# ANIMA_Small_Scale.net
KiCad netlist of a schematic drawn in EAGLE
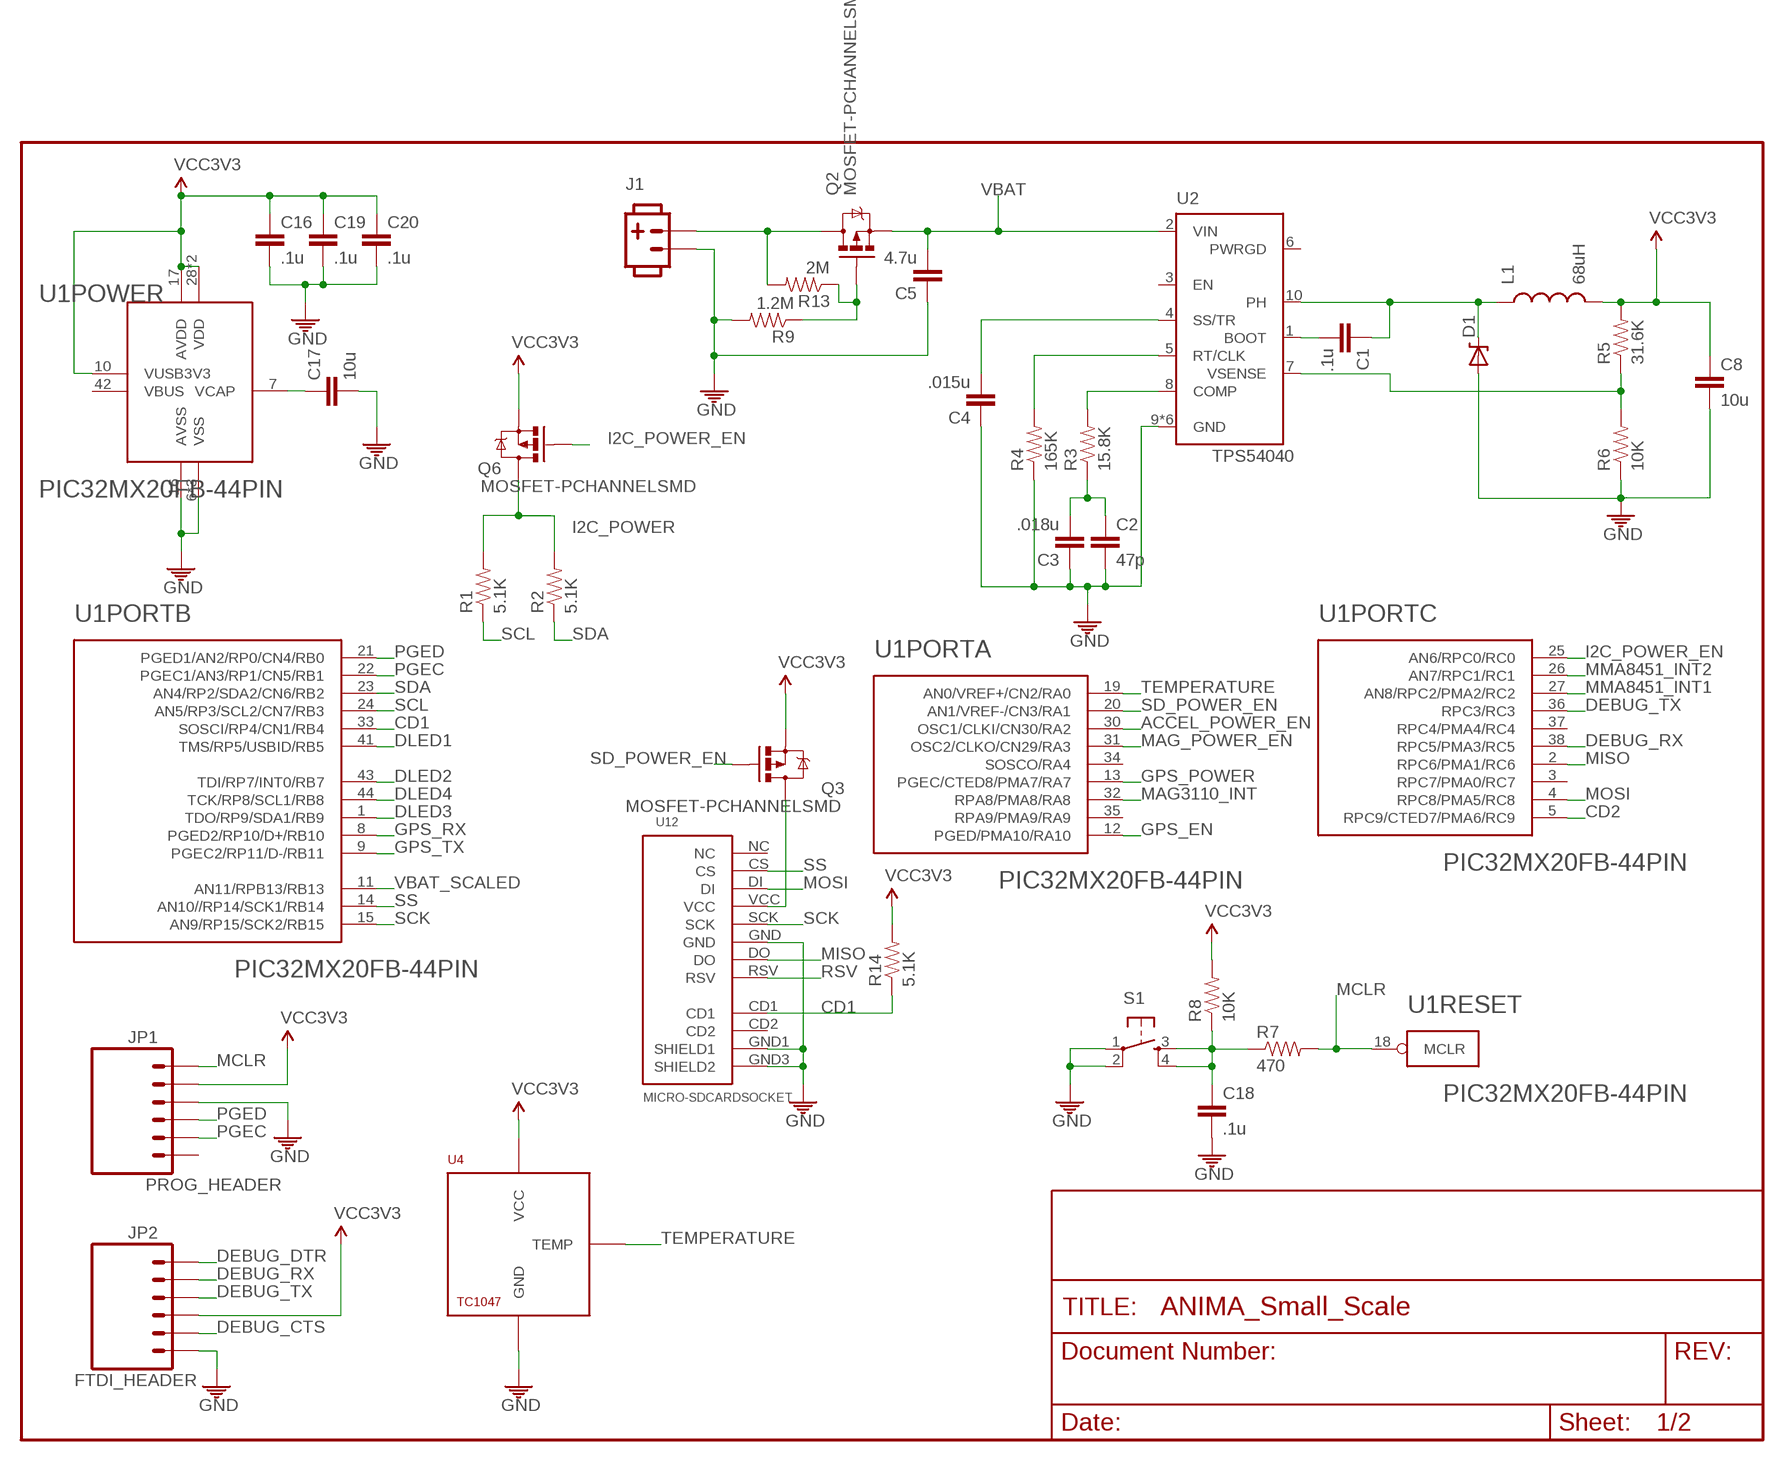
[diagram p0: schematic, sheet 1]
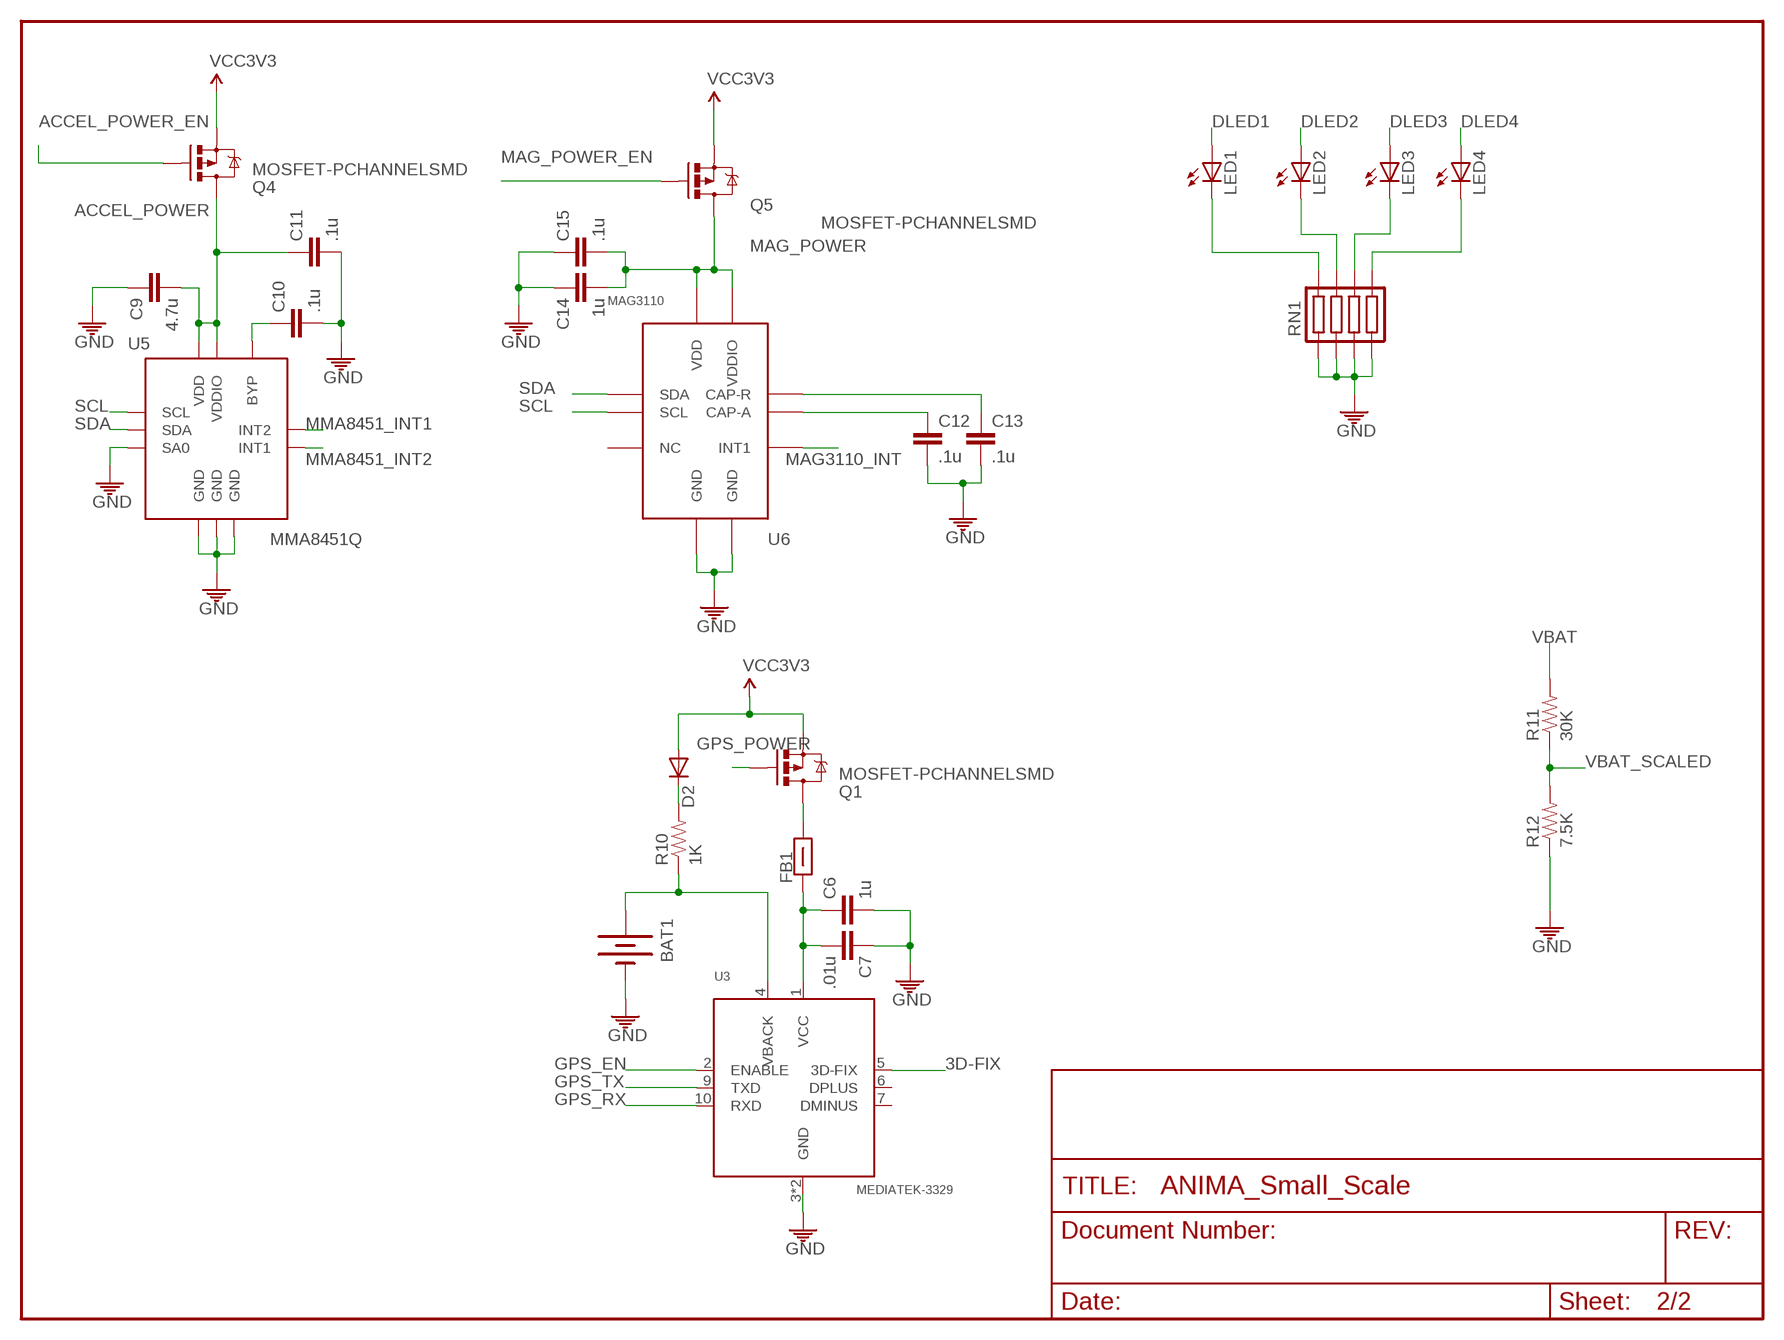
[diagram p1: schematic, sheet 2]

(export (version "E")
  (design (tool "Eeschema 10.0.6"))
  (components
    (comp (ref "BAT1")
      (value "BATTERY4.8MMSMD")
      (footprint "eagle-import:MS412FE-FL26E")
      (libsource (lib "eagle-import") (part "BATTERY4.8MMSMD"))
    )
    (comp (ref "C6")
      (value "1u")
      (footprint "eagle-import:0805")
      (libsource (lib "eagle-import") (part "CAP0805"))
    )
    (comp (ref "C7")
      (value ".01u")
      (footprint "eagle-import:0805")
      (libsource (lib "eagle-import") (part "CAP0805"))
    )
    (comp (ref "C9")
      (value "4.7u")
      (footprint "eagle-import:0805")
      (libsource (lib "eagle-import") (part "CAP0805"))
    )
    (comp (ref "C10")
      (value ".1u")
      (footprint "eagle-import:0805")
      (libsource (lib "eagle-import") (part "CAP0805"))
    )
    (comp (ref "C11")
      (value ".1u")
      (footprint "eagle-import:0805")
      (libsource (lib "eagle-import") (part "CAP0805"))
    )
    (comp (ref "C12")
      (value ".1u")
      (footprint "eagle-import:0805")
      (libsource (lib "eagle-import") (part "CAP0805"))
    )
    (comp (ref "C13")
      (value ".1u")
      (footprint "eagle-import:0805")
      (libsource (lib "eagle-import") (part "CAP0805"))
    )
    (comp (ref "C14")
      (value "1u")
      (footprint "eagle-import:0805")
      (libsource (lib "eagle-import") (part "CAP0805"))
    )
    (comp (ref "C15")
      (value ".1u")
      (footprint "eagle-import:0805")
      (libsource (lib "eagle-import") (part "CAP0805"))
    )
    (comp (ref "D2")
      (value "DIODESMA")
      (footprint "eagle-import:SMA-DIODE")
      (libsource (lib "eagle-import") (part "DIODESMA"))
    )
    (comp (ref "FB1")
      (value "FERRITE_BEAD")
      (footprint "eagle-import:0603")
      (libsource (lib "eagle-import") (part "FERRITE_BEAD"))
    )
    (comp (ref "LED1")
      (value "LED1206")
      (footprint "eagle-import:LED-1206")
      (libsource (lib "eagle-import") (part "LED1206"))
    )
    (comp (ref "LED2")
      (value "LED1206")
      (footprint "eagle-import:LED-1206")
      (libsource (lib "eagle-import") (part "LED1206"))
    )
    (comp (ref "LED3")
      (value "LED1206")
      (footprint "eagle-import:LED-1206")
      (libsource (lib "eagle-import") (part "LED1206"))
    )
    (comp (ref "LED4")
      (value "LED1206")
      (footprint "eagle-import:LED-1206")
      (libsource (lib "eagle-import") (part "LED1206"))
    )
    (comp (ref "Q1")
      (value "MOSFET-PCHANNELSMD")
      (footprint "eagle-import:SOT23-3")
      (libsource (lib "eagle-import") (part "MOSFET-PCHANNELSMD"))
    )
    (comp (ref "Q4")
      (value "MOSFET-PCHANNELSMD")
      (footprint "eagle-import:SOT23-3")
      (libsource (lib "eagle-import") (part "MOSFET-PCHANNELSMD"))
    )
    (comp (ref "Q5")
      (value "MOSFET-PCHANNELSMD")
      (footprint "eagle-import:SOT23-3")
      (libsource (lib "eagle-import") (part "MOSFET-PCHANNELSMD"))
    )
    (comp (ref "R10")
      (value "1K")
      (footprint "eagle-import:0805")
      (libsource (lib "eagle-import") (part "RESISTOR0805-RES"))
    )
    (comp (ref "R11")
      (value "30K")
      (footprint "eagle-import:0805")
      (libsource (lib "eagle-import") (part "RESISTOR0805-RES"))
    )
    (comp (ref "R12")
      (value "7.5K")
      (footprint "eagle-import:0805")
      (libsource (lib "eagle-import") (part "RESISTOR0805-RES"))
    )
    (comp (ref "RN1")
      (value "RESISTOR_ARRAY-4")
      (footprint "eagle-import:EXB-38V271JV")
      (libsource (lib "eagle-import") (part "RESISTOR_ARRAY-4"))
    )
    (comp (ref "U3")
      (value "MEDIATEK-3329")
      (footprint "eagle-import:MEDIATEK-3329")
      (libsource (lib "eagle-import") (part "MEDIATEK-3329"))
    )
    (comp (ref "U5")
      (value "MMA8451Q")
      (footprint "eagle-import:QFN-16_FREE")
      (libsource (lib "eagle-import") (part "MMA8451Q"))
    )
    (comp (ref "U6")
      (value "MAG3110")
      (footprint "eagle-import:DFN-10_FREE")
      (libsource (lib "eagle-import") (part "MAG3110"))
    )
    (comp (ref "C1")
      (value ".1u")
      (footprint "eagle-import:0805")
      (libsource (lib "eagle-import") (part "CAP0805"))
    )
    (comp (ref "C2")
      (value "47p")
      (footprint "eagle-import:0805")
      (libsource (lib "eagle-import") (part "CAP0805"))
    )
    (comp (ref "C3")
      (value ".018u")
      (footprint "eagle-import:0805")
      (libsource (lib "eagle-import") (part "CAP0805"))
    )
    (comp (ref "C4")
      (value ".015u")
      (footprint "eagle-import:0805")
      (libsource (lib "eagle-import") (part "CAP0805"))
    )
    (comp (ref "C5")
      (value "4.7u")
      (footprint "eagle-import:0805")
      (libsource (lib "eagle-import") (part "CAP0805"))
    )
    (comp (ref "C8")
      (value "10u")
      (footprint "eagle-import:1206")
      (libsource (lib "eagle-import") (part "CAP1206"))
    )
    (comp (ref "C16")
      (value ".1u")
      (footprint "eagle-import:0805")
      (libsource (lib "eagle-import") (part "CAP0805"))
    )
    (comp (ref "C17")
      (value "10u")
      (footprint "eagle-import:0805")
      (libsource (lib "eagle-import") (part "CAP0805"))
    )
    (comp (ref "C18")
      (value ".1u")
      (footprint "eagle-import:0805")
      (libsource (lib "eagle-import") (part "CAP0805"))
    )
    (comp (ref "C19")
      (value ".1u")
      (footprint "eagle-import:0805")
      (libsource (lib "eagle-import") (part "CAP0805"))
    )
    (comp (ref "C20")
      (value ".1u")
      (footprint "eagle-import:0805")
      (libsource (lib "eagle-import") (part "CAP0805"))
    )
    (comp (ref "D1")
      (value "DIODE-ZENER1")
      (footprint "eagle-import:SOD523")
      (libsource (lib "eagle-import") (part "DIODE-ZENER1"))
    )
    (comp (ref "J1")
      (value "POW_CONNECTFEMALE-RA")
      (footprint "eagle-import:SOCKET-FEMALE_RA-3.96MM-2")
      (libsource (lib "eagle-import") (part "POW_CONNECTFEMALE-RA"))
    )
    (comp (ref "JP1")
      (value "M06FEMALE_LOCK")
      (footprint "eagle-import:1X06_FEMALE_LOCK.010")
      (libsource (lib "eagle-import") (part "M06FEMALE_LOCK"))
    )
    (comp (ref "JP2")
      (value "M06FEMALE_LOCK")
      (footprint "eagle-import:1X06_FEMALE_LOCK.010")
      (libsource (lib "eagle-import") (part "M06FEMALE_LOCK"))
    )
    (comp (ref "L1")
      (value "68uH")
      (footprint "eagle-import:ELL-CTVV")
      (libsource (lib "eagle-import") (part "INDUCTORELL-CTVV"))
    )
    (comp (ref "Q2")
      (value "MOSFET-PCHANNELSMD")
      (footprint "eagle-import:SOT23-3")
      (libsource (lib "eagle-import") (part "MOSFET-PCHANNELSMD"))
    )
    (comp (ref "Q3")
      (value "MOSFET-PCHANNELSMD")
      (footprint "eagle-import:SOT23-3")
      (libsource (lib "eagle-import") (part "MOSFET-PCHANNELSMD"))
    )
    (comp (ref "Q6")
      (value "MOSFET-PCHANNELSMD")
      (footprint "eagle-import:SOT23-3")
      (libsource (lib "eagle-import") (part "MOSFET-PCHANNELSMD"))
    )
    (comp (ref "R1")
      (value "5.1K")
      (footprint "eagle-import:0805")
      (libsource (lib "eagle-import") (part "RESISTOR0805-RES"))
    )
    (comp (ref "R2")
      (value "5.1K")
      (footprint "eagle-import:0805")
      (libsource (lib "eagle-import") (part "RESISTOR0805-RES"))
    )
    (comp (ref "R3")
      (value "15.8K")
      (footprint "eagle-import:0805")
      (libsource (lib "eagle-import") (part "RESISTOR0805-RES"))
    )
    (comp (ref "R4")
      (value "165K")
      (footprint "eagle-import:0805")
      (libsource (lib "eagle-import") (part "RESISTOR0805-RES"))
    )
    (comp (ref "R5")
      (value "31.6K")
      (footprint "eagle-import:0805")
      (libsource (lib "eagle-import") (part "RESISTOR0805-RES"))
    )
    (comp (ref "R6")
      (value "10K")
      (footprint "eagle-import:0805")
      (libsource (lib "eagle-import") (part "RESISTOR0805-RES"))
    )
    (comp (ref "R7")
      (value "470")
      (footprint "eagle-import:0805")
      (libsource (lib "eagle-import") (part "RESISTOR0805-RES"))
    )
    (comp (ref "R8")
      (value "10K")
      (footprint "eagle-import:0805")
      (libsource (lib "eagle-import") (part "RESISTOR0805-RES"))
    )
    (comp (ref "R9")
      (value "1.2M")
      (footprint "eagle-import:0805")
      (libsource (lib "eagle-import") (part "RESISTOR0805-RES"))
    )
    (comp (ref "R13")
      (value "2M")
      (footprint "eagle-import:0805")
      (libsource (lib "eagle-import") (part "RESISTOR0805-RES"))
    )
    (comp (ref "R14")
      (value "5.1K")
      (footprint "eagle-import:0805")
      (libsource (lib "eagle-import") (part "RESISTOR0805-RES"))
    )
    (comp (ref "S1")
      (value "TAC_SWITCHPTH")
      (footprint "eagle-import:B3F-1020")
      (libsource (lib "eagle-import") (part "TAC_SWITCHPTH"))
    )
    (comp (ref "U1")
      (value "PIC32MX20FB-44PIN")
      (footprint "eagle-import:TQFP44")
      (libsource (lib "eagle-import") (part "PIC32MX20FB-44PIN"))
    )
    (comp (ref "U2")
      (value "TPS54040")
      (footprint "eagle-import:MSOP-10-GNDPAD")
      (libsource (lib "eagle-import") (part "TPS54040"))
    )
    (comp (ref "U4")
      (value "TC1047")
      (footprint "eagle-import:SOT-23B")
      (libsource (lib "eagle-import") (part "TC1047"))
    )
    (comp (ref "U12")
      (value "MICRO-SDCARDSOCKET")
      (footprint "eagle-import:MICRO-SD-SOCKET-PP")
      (libsource (lib "eagle-import") (part "MICRO-SDCARDSOCKET"))
    )
  )
  (nets
    (net (code "1") (name "3D-FIX") (class "Default")
      (node (ref "U3") (pin "5") (pinfunction "3D-FIX_5") (pintype "output"))
    )
    (net (code "2") (name "ACCEL_POWER") (class "Default")
      (node (ref "C11") (pin "1") (pinfunction "1_1") (pintype "passive"))
      (node (ref "C9") (pin "2") (pinfunction "2_2") (pintype "passive"))
      (node (ref "Q4") (pin "3") (pinfunction "D_3") (pintype "passive"))
      (node (ref "U5") (pin "P$1") (pinfunction "VDDIO_P$1") (pintype "passive"))
      (node (ref "U5") (pin "P$14") (pinfunction "VDD_P$14") (pintype "passive"))
    )
    (net (code "3") (name "ACCEL_POWER_EN") (class "Default")
      (node (ref "Q4") (pin "1") (pinfunction "G_1") (pintype "passive"))
      (node (ref "U1") (pin "30") (pinfunction "OSC1/CLKI/CN30/RA2_30") (pintype "bidirectional"))
    )
    (net (code "4") (name "CD1") (class "Default")
      (node (ref "R14") (pin "1") (pinfunction "1_1") (pintype "passive"))
      (node (ref "U1") (pin "33") (pinfunction "SOSCI/RP4/CN1/RB4_33") (pintype "bidirectional"))
      (node (ref "U12") (pin "CD1") (pinfunction "CD1_CD1") (pintype "bidirectional"))
    )
    (net (code "5") (name "CD2") (class "Default")
      (node (ref "U1") (pin "5") (pinfunction "RPC9/CTED7/PMA6/RC9_5") (pintype "bidirectional"))
    )
    (net (code "6") (name "DEBUG_CTS") (class "Default")
      (node (ref "JP2") (pin "5") (pinfunction "5_5") (pintype "passive"))
    )
    (net (code "7") (name "DEBUG_DTR") (class "Default")
      (node (ref "JP2") (pin "1") (pinfunction "1_1") (pintype "passive"))
    )
    (net (code "8") (name "DEBUG_RX") (class "Default")
      (node (ref "JP2") (pin "2") (pinfunction "2_2") (pintype "passive"))
      (node (ref "U1") (pin "38") (pinfunction "RPC5/PMA3/RC5_38") (pintype "bidirectional"))
    )
    (net (code "9") (name "DEBUG_TX") (class "Default")
      (node (ref "JP2") (pin "3") (pinfunction "3_3") (pintype "passive"))
      (node (ref "U1") (pin "36") (pinfunction "RPC3/RC3_36") (pintype "bidirectional"))
    )
    (net (code "10") (name "DLED1") (class "Default")
      (node (ref "LED1") (pin "A") (pinfunction "A_A") (pintype "passive"))
      (node (ref "U1") (pin "41") (pinfunction "TMS/RP5/USBID/RB5_41") (pintype "bidirectional"))
    )
    (net (code "11") (name "DLED2") (class "Default")
      (node (ref "LED2") (pin "A") (pinfunction "A_A") (pintype "passive"))
      (node (ref "U1") (pin "43") (pinfunction "TDI/RP7/INT0/RB7_43") (pintype "bidirectional"))
    )
    (net (code "12") (name "DLED3") (class "Default")
      (node (ref "LED3") (pin "A") (pinfunction "A_A") (pintype "passive"))
      (node (ref "U1") (pin "1") (pinfunction "TDO/RP9/SDA1/RB9_1") (pintype "bidirectional"))
    )
    (net (code "13") (name "DLED4") (class "Default")
      (node (ref "LED4") (pin "A") (pinfunction "A_A") (pintype "passive"))
      (node (ref "U1") (pin "44") (pinfunction "TCK/RP8/SCL1/RB8_44") (pintype "bidirectional"))
    )
    (net (code "14") (name "GND") (class "Default")
      (node (ref "BAT1") (pin "-") (pinfunction "-_-") (pintype "power_in"))
      (node (ref "C10") (pin "2") (pinfunction "2_2") (pintype "passive"))
      (node (ref "C11") (pin "2") (pinfunction "2_2") (pintype "passive"))
      (node (ref "C12") (pin "2") (pinfunction "2_2") (pintype "passive"))
      (node (ref "C13") (pin "2") (pinfunction "2_2") (pintype "passive"))
      (node (ref "C14") (pin "1") (pinfunction "1_1") (pintype "passive"))
      (node (ref "C15") (pin "1") (pinfunction "1_1") (pintype "passive"))
      (node (ref "C16") (pin "2") (pinfunction "2_2") (pintype "passive"))
      (node (ref "C17") (pin "2") (pinfunction "2_2") (pintype "passive"))
      (node (ref "C18") (pin "2") (pinfunction "2_2") (pintype "passive"))
      (node (ref "C19") (pin "2") (pinfunction "2_2") (pintype "passive"))
      (node (ref "C2") (pin "2") (pinfunction "2_2") (pintype "passive"))
      (node (ref "C20") (pin "2") (pinfunction "2_2") (pintype "passive"))
      (node (ref "C3") (pin "1") (pinfunction "1_1") (pintype "passive"))
      (node (ref "C4") (pin "1") (pinfunction "1_1") (pintype "passive"))
      (node (ref "C5") (pin "1") (pinfunction "1_1") (pintype "passive"))
      (node (ref "C6") (pin "2") (pinfunction "2_2") (pintype "passive"))
      (node (ref "C7") (pin "1") (pinfunction "1_1") (pintype "passive"))
      (node (ref "C8") (pin "2") (pinfunction "2_2") (pintype "passive"))
      (node (ref "C9") (pin "1") (pinfunction "1_1") (pintype "passive"))
      (node (ref "D1") (pin "-") (pinfunction "A_-") (pintype "passive"))
      (node (ref "J1") (pin "2") (pinfunction "2_2") (pintype "passive"))
      (node (ref "JP1") (pin "3") (pinfunction "3_3") (pintype "passive"))
      (node (ref "JP2") (pin "6") (pinfunction "6_6") (pintype "passive"))
      (node (ref "R12") (pin "1") (pinfunction "1_1") (pintype "passive"))
      (node (ref "R4") (pin "1") (pinfunction "1_1") (pintype "passive"))
      (node (ref "R6") (pin "1") (pinfunction "1_1") (pintype "passive"))
      (node (ref "R9") (pin "2") (pinfunction "2_2") (pintype "passive"))
      (node (ref "RN1") (pin "P$1") (pinfunction "1_P$1") (pintype "passive"))
      (node (ref "RN1") (pin "P$2") (pinfunction "2_P$2") (pintype "passive"))
      (node (ref "RN1") (pin "P$3") (pinfunction "3_P$3") (pintype "passive"))
      (node (ref "RN1") (pin "P$4") (pinfunction "4_P$4") (pintype "passive"))
      (node (ref "S1") (pin "1") (pinfunction "1_1") (pintype "passive"))
      (node (ref "S1") (pin "2") (pinfunction "2_2") (pintype "passive"))
      (node (ref "U1") (pin "16") (pinfunction "AVSS_16") (pintype "bidirectional"))
      (node (ref "U1") (pin "29") (pinfunction "VSS_29") (pintype "bidirectional"))
      (node (ref "U1") (pin "39") (pinfunction "VSS_39") (pintype "bidirectional"))
      (node (ref "U1") (pin "6") (pinfunction "VSS_6") (pintype "bidirectional"))
      (node (ref "U12") (pin "GND") (pinfunction "GND_GND") (pintype "bidirectional"))
      (node (ref "U12") (pin "GND1") (pinfunction "SHIELD1_GND1") (pintype "bidirectional"))
      (node (ref "U12") (pin "GND3") (pinfunction "SHIELD2_GND3") (pintype "bidirectional"))
      (node (ref "U2") (pin "9") (pinfunction "GND_9") (pintype "power_in"))
      (node (ref "U2") (pin "GND") (pinfunction "GND_GND") (pintype "power_in"))
      (node (ref "U2") (pin "GND@1") (pinfunction "GND_GND@1") (pintype "power_in"))
      (node (ref "U2") (pin "GND@2") (pinfunction "GND_GND@2") (pintype "power_in"))
      (node (ref "U2") (pin "GND@3") (pinfunction "GND_GND@3") (pintype "power_in"))
      (node (ref "U2") (pin "GND@4") (pinfunction "GND_GND@4") (pintype "power_in"))
      (node (ref "U3") (pin "3") (pinfunction "GND_3") (pintype "power_in"))
      (node (ref "U3") (pin "8") (pinfunction "GND_8") (pintype "power_in"))
      (node (ref "U4") (pin "P$3") (pinfunction "GND_P$3") (pintype "power_in"))
      (node (ref "U5") (pin "P$10") (pinfunction "GND_P$10") (pintype "passive"))
      (node (ref "U5") (pin "P$12") (pinfunction "GND_P$12") (pintype "passive"))
      (node (ref "U5") (pin "P$5") (pinfunction "GND_P$5") (pintype "passive"))
      (node (ref "U5") (pin "P$7") (pinfunction "SA0_P$7") (pintype "bidirectional"))
      (node (ref "U6") (pin "P$10") (pinfunction "GND_P$10") (pintype "passive"))
      (node (ref "U6") (pin "P$5") (pinfunction "GND_P$5") (pintype "passive"))
    )
    (net (code "15") (name "GPS_EN") (class "Default")
      (node (ref "U1") (pin "12") (pinfunction "PGED/PMA10/RA10_12") (pintype "bidirectional"))
      (node (ref "U3") (pin "2") (pinfunction "ENABLE_2") (pintype "input"))
    )
    (net (code "16") (name "GPS_POWER") (class "Default")
      (node (ref "Q1") (pin "1") (pinfunction "G_1") (pintype "passive"))
      (node (ref "U1") (pin "13") (pinfunction "PGEC/CTED8/PMA7/RA7_13") (pintype "bidirectional"))
    )
    (net (code "17") (name "GPS_RX") (class "Default")
      (node (ref "U1") (pin "8") (pinfunction "PGED2/RP10/D+/RB10_8") (pintype "bidirectional"))
      (node (ref "U3") (pin "10") (pinfunction "RXD_10") (pintype "input"))
    )
    (net (code "18") (name "GPS_TX") (class "Default")
      (node (ref "U1") (pin "9") (pinfunction "PGEC2/RP11/D-/RB11_9") (pintype "bidirectional"))
      (node (ref "U3") (pin "9") (pinfunction "TXD_9") (pintype "output"))
    )
    (net (code "19") (name "I2C_POWER") (class "Default")
      (node (ref "Q6") (pin "3") (pinfunction "D_3") (pintype "passive"))
      (node (ref "R1") (pin "2") (pinfunction "2_2") (pintype "passive"))
      (node (ref "R2") (pin "2") (pinfunction "2_2") (pintype "passive"))
    )
    (net (code "20") (name "I2C_POWER_EN") (class "Default")
      (node (ref "Q6") (pin "1") (pinfunction "G_1") (pintype "passive"))
      (node (ref "U1") (pin "25") (pinfunction "AN6/RPC0/RC0_25") (pintype "bidirectional"))
    )
    (net (code "21") (name "MAG3110_INT") (class "Default")
      (node (ref "U1") (pin "32") (pinfunction "RPA8/PMA8/RA8_32") (pintype "bidirectional"))
      (node (ref "U6") (pin "P$9") (pinfunction "INT1_P$9") (pintype "passive"))
    )
    (net (code "22") (name "MAG_POWER") (class "Default")
      (node (ref "C14") (pin "2") (pinfunction "2_2") (pintype "passive"))
      (node (ref "C15") (pin "2") (pinfunction "2_2") (pintype "passive"))
      (node (ref "Q5") (pin "3") (pinfunction "D_3") (pintype "passive"))
      (node (ref "U6") (pin "P$2") (pinfunction "VDD_P$2") (pintype "passive"))
      (node (ref "U6") (pin "P$8") (pinfunction "VDDIO_P$8") (pintype "passive"))
    )
    (net (code "23") (name "MAG_POWER_EN") (class "Default")
      (node (ref "Q5") (pin "1") (pinfunction "G_1") (pintype "passive"))
      (node (ref "U1") (pin "31") (pinfunction "OSC2/CLKO/CN29/RA3_31") (pintype "bidirectional"))
    )
    (net (code "24") (name "MCLR") (class "Default")
      (node (ref "JP1") (pin "1") (pinfunction "1_1") (pintype "passive"))
      (node (ref "R7") (pin "2") (pinfunction "2_2") (pintype "passive"))
      (node (ref "U1") (pin "18") (pinfunction "MCLR_18") (pintype "bidirectional"))
    )
    (net (code "25") (name "MISO") (class "Default")
      (node (ref "U1") (pin "2") (pinfunction "RPC6/PMA1/RC6_2") (pintype "bidirectional"))
      (node (ref "U12") (pin "DO") (pinfunction "DO_DO") (pintype "bidirectional"))
    )
    (net (code "26") (name "MMA8451_INT1") (class "Default")
      (node (ref "U1") (pin "27") (pinfunction "AN8/RPC2/PMA2/RC2_27") (pintype "bidirectional"))
      (node (ref "U5") (pin "P$9") (pinfunction "INT2_P$9") (pintype "bidirectional"))
    )
    (net (code "27") (name "MMA8451_INT2") (class "Default")
      (node (ref "U1") (pin "26") (pinfunction "AN7/RPC1/RC1_26") (pintype "bidirectional"))
      (node (ref "U5") (pin "P$11") (pinfunction "INT1_P$11") (pintype "bidirectional"))
    )
    (net (code "28") (name "MOSI") (class "Default")
      (node (ref "U1") (pin "4") (pinfunction "RPC8/PMA5/RC8_4") (pintype "bidirectional"))
      (node (ref "U12") (pin "DI") (pinfunction "DI_DI") (pintype "bidirectional"))
    )
    (net (code "29") (name "Net-(C2-Pad1)") (class "Default")
      (node (ref "C2") (pin "1") (pinfunction "1_1") (pintype "passive"))
      (node (ref "C3") (pin "2") (pinfunction "2_2") (pintype "passive"))
      (node (ref "R3") (pin "1") (pinfunction "1_1") (pintype "passive"))
    )
    (net (code "30") (name "Net-(C18-Pad1)") (class "Default")
      (node (ref "C18") (pin "1") (pinfunction "1_1") (pintype "passive"))
      (node (ref "R7") (pin "1") (pinfunction "1_1") (pintype "passive"))
      (node (ref "R8") (pin "1") (pinfunction "1_1") (pintype "passive"))
      (node (ref "S1") (pin "3") (pinfunction "3_3") (pintype "passive"))
      (node (ref "S1") (pin "4") (pinfunction "4_4") (pintype "passive"))
    )
    (net (code "31") (name "Net-(D1-C)") (class "Default")
      (node (ref "C1") (pin "1") (pinfunction "1_1") (pintype "passive"))
      (node (ref "D1") (pin "+") (pinfunction "C_+") (pintype "passive"))
      (node (ref "L1") (pin "P$1") (pinfunction "1_P$1") (pintype "passive"))
      (node (ref "U2") (pin "10") (pinfunction "PH_10") (pintype "output"))
    )
    (net (code "32") (name "Net-(D2-PadC)") (class "Default")
      (node (ref "D2") (pin "C") (pinfunction "C_C") (pintype "passive"))
      (node (ref "R10") (pin "2") (pinfunction "2_2") (pintype "passive"))
    )
    (net (code "33") (name "Net-(Q1-D)") (class "Default")
      (node (ref "FB1") (pin "2") (pinfunction "2_2") (pintype "passive"))
      (node (ref "Q1") (pin "3") (pinfunction "D_3") (pintype "passive"))
    )
    (net (code "34") (name "Net-(Q2-D)") (class "Default")
      (node (ref "J1") (pin "1") (pinfunction "1_1") (pintype "passive"))
      (node (ref "Q2") (pin "3") (pinfunction "D_3") (pintype "passive"))
      (node (ref "R13") (pin "2") (pinfunction "2_2") (pintype "passive"))
    )
    (net (code "35") (name "Net-(Q2-G)") (class "Default")
      (node (ref "Q2") (pin "1") (pinfunction "G_1") (pintype "passive"))
      (node (ref "R13") (pin "1") (pinfunction "1_1") (pintype "passive"))
      (node (ref "R9") (pin "1") (pinfunction "1_1") (pintype "passive"))
    )
    (net (code "36") (name "Net-(Q3-D)") (class "Default")
      (node (ref "Q3") (pin "3") (pinfunction "D_3") (pintype "passive"))
      (node (ref "U12") (pin "VCC") (pinfunction "VCC_VCC") (pintype "bidirectional"))
    )
    (net (code "37") (name "Net-(RN1-5)") (class "Default")
      (node (ref "LED4") (pin "C") (pinfunction "C_C") (pintype "passive"))
      (node (ref "RN1") (pin "P$5") (pinfunction "5_P$5") (pintype "passive"))
    )
    (net (code "38") (name "Net-(RN1-6)") (class "Default")
      (node (ref "LED3") (pin "C") (pinfunction "C_C") (pintype "passive"))
      (node (ref "RN1") (pin "P$6") (pinfunction "6_P$6") (pintype "passive"))
    )
    (net (code "39") (name "Net-(RN1-7)") (class "Default")
      (node (ref "LED2") (pin "C") (pinfunction "C_C") (pintype "passive"))
      (node (ref "RN1") (pin "P$7") (pinfunction "7_P$7") (pintype "passive"))
    )
    (net (code "40") (name "Net-(RN1-8)") (class "Default")
      (node (ref "LED1") (pin "C") (pinfunction "C_C") (pintype "passive"))
      (node (ref "RN1") (pin "P$8") (pinfunction "8_P$8") (pintype "passive"))
    )
    (net (code "41") (name "Net-(U1D-VCAP)") (class "Default")
      (node (ref "C17") (pin "1") (pinfunction "1_1") (pintype "passive"))
      (node (ref "U1") (pin "7") (pinfunction "VCAP_7") (pintype "bidirectional"))
    )
    (net (code "42") (name "Net-(U2-BOOT)") (class "Default")
      (node (ref "C1") (pin "2") (pinfunction "2_2") (pintype "passive"))
      (node (ref "U2") (pin "1") (pinfunction "BOOT_1") (pintype "output"))
    )
    (net (code "43") (name "Net-(U2-COMP)") (class "Default")
      (node (ref "R3") (pin "2") (pinfunction "2_2") (pintype "passive"))
      (node (ref "U2") (pin "8") (pinfunction "COMP_8") (pintype "bidirectional"))
    )
    (net (code "44") (name "Net-(U2-RT{slash}CLK)") (class "Default")
      (node (ref "R4") (pin "2") (pinfunction "2_2") (pintype "passive"))
      (node (ref "U2") (pin "5") (pinfunction "RT/CLK_5") (pintype "bidirectional"))
    )
    (net (code "45") (name "Net-(U2-SS{slash}TR)") (class "Default")
      (node (ref "C4") (pin "2") (pinfunction "2_2") (pintype "passive"))
      (node (ref "U2") (pin "4") (pinfunction "SS/TR_4") (pintype "bidirectional"))
    )
    (net (code "46") (name "Net-(U2-VSENSE)") (class "Default")
      (node (ref "R5") (pin "1") (pinfunction "1_1") (pintype "passive"))
      (node (ref "R6") (pin "2") (pinfunction "2_2") (pintype "passive"))
      (node (ref "U2") (pin "7") (pinfunction "VSENSE_7") (pintype "input"))
    )
    (net (code "47") (name "Net-(U3-VBACK)") (class "Default")
      (node (ref "BAT1") (pin "+") (pinfunction "+_+") (pintype "power_in"))
      (node (ref "R10") (pin "1") (pinfunction "1_1") (pintype "passive"))
      (node (ref "U3") (pin "4") (pinfunction "VBACK_4") (pintype "power_in"))
    )
    (net (code "48") (name "Net-(U3-VCC)") (class "Default")
      (node (ref "C6") (pin "1") (pinfunction "1_1") (pintype "passive"))
      (node (ref "C7") (pin "2") (pinfunction "2_2") (pintype "passive"))
      (node (ref "FB1") (pin "1") (pinfunction "1_1") (pintype "passive"))
      (node (ref "U3") (pin "1") (pinfunction "VCC_1") (pintype "power_in"))
    )
    (net (code "49") (name "Net-(U5-BYP)") (class "Default")
      (node (ref "C10") (pin "1") (pinfunction "1_1") (pintype "passive"))
      (node (ref "U5") (pin "P$2") (pinfunction "BYP_P$2") (pintype "bidirectional"))
    )
    (net (code "50") (name "Net-(U6-CAP-A)") (class "Default")
      (node (ref "C12") (pin "1") (pinfunction "1_1") (pintype "passive"))
      (node (ref "U6") (pin "P$1") (pinfunction "CAP-A_P$1") (pintype "passive"))
    )
    (net (code "51") (name "Net-(U6-CAP-R)") (class "Default")
      (node (ref "C13") (pin "1") (pinfunction "1_1") (pintype "passive"))
      (node (ref "U6") (pin "P$4") (pinfunction "CAP-R_P$4") (pintype "passive"))
    )
    (net (code "52") (name "PGEC") (class "Default")
      (node (ref "JP1") (pin "5") (pinfunction "5_5") (pintype "passive"))
      (node (ref "U1") (pin "22") (pinfunction "PGEC1/AN3/RP1/CN5/RB1_22") (pintype "bidirectional"))
    )
    (net (code "53") (name "PGED") (class "Default")
      (node (ref "JP1") (pin "4") (pinfunction "4_4") (pintype "passive"))
      (node (ref "U1") (pin "21") (pinfunction "PGED1/AN2/RP0/CN4/RB0_21") (pintype "bidirectional"))
    )
    (net (code "54") (name "RSV") (class "Default")
      (node (ref "U12") (pin "RSV") (pinfunction "RSV_RSV") (pintype "bidirectional"))
    )
    (net (code "55") (name "SCK") (class "Default")
      (node (ref "U1") (pin "15") (pinfunction "AN9/RP15/SCK2/RB15_15") (pintype "bidirectional"))
      (node (ref "U12") (pin "SCK") (pinfunction "SCK_SCK") (pintype "bidirectional"))
    )
    (net (code "56") (name "SCL") (class "Default")
      (node (ref "R1") (pin "1") (pinfunction "1_1") (pintype "passive"))
      (node (ref "U1") (pin "24") (pinfunction "AN5/RP3/SCL2/CN7/RB3_24") (pintype "bidirectional"))
      (node (ref "U5") (pin "P$4") (pinfunction "SCL_P$4") (pintype "bidirectional"))
      (node (ref "U6") (pin "P$7") (pinfunction "SCL_P$7") (pintype "passive"))
    )
    (net (code "57") (name "SDA") (class "Default")
      (node (ref "R2") (pin "1") (pinfunction "1_1") (pintype "passive"))
      (node (ref "U1") (pin "23") (pinfunction "AN4/RP2/SDA2/CN6/RB2_23") (pintype "bidirectional"))
      (node (ref "U5") (pin "P$6") (pinfunction "SDA_P$6") (pintype "bidirectional"))
      (node (ref "U6") (pin "P$6") (pinfunction "SDA_P$6") (pintype "passive"))
    )
    (net (code "58") (name "SD_POWER_EN") (class "Default")
      (node (ref "Q3") (pin "1") (pinfunction "G_1") (pintype "passive"))
      (node (ref "U1") (pin "20") (pinfunction "AN1/VREF-/CN3/RA1_20") (pintype "bidirectional"))
    )
    (net (code "59") (name "SS") (class "Default")
      (node (ref "U1") (pin "14") (pinfunction "AN10//RP14/SCK1/RB14_14") (pintype "bidirectional"))
      (node (ref "U12") (pin "CS") (pinfunction "CS_CS") (pintype "bidirectional"))
    )
    (net (code "60") (name "TEMPERATURE") (class "Default")
      (node (ref "U1") (pin "19") (pinfunction "AN0/VREF+/CN2/RA0_19") (pintype "bidirectional"))
      (node (ref "U4") (pin "P$2") (pinfunction "TEMP_P$2") (pintype "output"))
    )
    (net (code "61") (name "VBAT") (class "Default")
      (node (ref "C5") (pin "2") (pinfunction "2_2") (pintype "passive"))
      (node (ref "Q2") (pin "2") (pinfunction "S_2") (pintype "passive"))
      (node (ref "R11") (pin "2") (pinfunction "2_2") (pintype "passive"))
      (node (ref "U2") (pin "2") (pinfunction "VIN_2") (pintype "input"))
    )
    (net (code "62") (name "VBAT_SCALED") (class "Default")
      (node (ref "R11") (pin "1") (pinfunction "1_1") (pintype "passive"))
      (node (ref "R12") (pin "2") (pinfunction "2_2") (pintype "passive"))
      (node (ref "U1") (pin "11") (pinfunction "AN11/RPB13/RB13_11") (pintype "bidirectional"))
    )
    (net (code "63") (name "VCC3V3") (class "Default")
      (node (ref "C16") (pin "1") (pinfunction "1_1") (pintype "passive"))
      (node (ref "C19") (pin "1") (pinfunction "1_1") (pintype "passive"))
      (node (ref "C20") (pin "1") (pinfunction "1_1") (pintype "passive"))
      (node (ref "C8") (pin "1") (pinfunction "1_1") (pintype "passive"))
      (node (ref "D2") (pin "A") (pinfunction "A_A") (pintype "passive"))
      (node (ref "JP1") (pin "2") (pinfunction "2_2") (pintype "passive"))
      (node (ref "JP2") (pin "4") (pinfunction "4_4") (pintype "passive"))
      (node (ref "L1") (pin "P$2") (pinfunction "2_P$2") (pintype "passive"))
      (node (ref "Q1") (pin "2") (pinfunction "S_2") (pintype "passive"))
      (node (ref "Q3") (pin "2") (pinfunction "S_2") (pintype "passive"))
      (node (ref "Q4") (pin "2") (pinfunction "S_2") (pintype "passive"))
      (node (ref "Q5") (pin "2") (pinfunction "S_2") (pintype "passive"))
      (node (ref "Q6") (pin "2") (pinfunction "S_2") (pintype "passive"))
      (node (ref "R14") (pin "2") (pinfunction "2_2") (pintype "passive"))
      (node (ref "R5") (pin "2") (pinfunction "2_2") (pintype "passive"))
      (node (ref "R8") (pin "2") (pinfunction "2_2") (pintype "passive"))
      (node (ref "U1") (pin "10") (pinfunction "VUSB3V3_10") (pintype "bidirectional"))
      (node (ref "U1") (pin "17") (pinfunction "AVDD_17") (pintype "bidirectional"))
      (node (ref "U1") (pin "28") (pinfunction "VDD_28") (pintype "bidirectional"))
      (node (ref "U1") (pin "40") (pinfunction "VDD_40") (pintype "bidirectional"))
      (node (ref "U4") (pin "P$1") (pinfunction "VCC_P$1") (pintype "power_in"))
    )
    (net (code "64") (name "unconnected-(JP1-Pad6)") (class "Default")
      (node (ref "JP1") (pin "6") (pinfunction "6_6") (pintype "passive"))
    )
    (net (code "65") (name "unconnected-(U1A-RPA9{slash}PMA9{slash}RA9-Pad35)") (class "Default")
      (node (ref "U1") (pin "35") (pinfunction "RPA9/PMA9/RA9_35") (pintype "bidirectional"))
    )
    (net (code "66") (name "unconnected-(U1A-SOSCO{slash}RA4-Pad34)") (class "Default")
      (node (ref "U1") (pin "34") (pinfunction "SOSCO/RA4_34") (pintype "bidirectional"))
    )
    (net (code "67") (name "unconnected-(U1C-RPC4{slash}PMA4{slash}RC4-Pad37)") (class "Default")
      (node (ref "U1") (pin "37") (pinfunction "RPC4/PMA4/RC4_37") (pintype "bidirectional"))
    )
    (net (code "68") (name "unconnected-(U1C-RPC7{slash}PMA0{slash}RC7-Pad3)") (class "Default")
      (node (ref "U1") (pin "3") (pinfunction "RPC7/PMA0/RC7_3") (pintype "bidirectional"))
    )
    (net (code "69") (name "unconnected-(U1D-VBUS-Pad42)") (class "Default")
      (node (ref "U1") (pin "42") (pinfunction "VBUS_42") (pintype "bidirectional"))
    )
    (net (code "70") (name "unconnected-(U2-EN-Pad3)") (class "Default")
      (node (ref "U2") (pin "3") (pinfunction "EN_3") (pintype "input"))
    )
    (net (code "71") (name "unconnected-(U2-PWRGD-Pad6)") (class "Default")
      (node (ref "U2") (pin "6") (pinfunction "PWRGD_6") (pintype "output"))
    )
    (net (code "72") (name "unconnected-(U3-DMINUS-Pad7)") (class "Default")
      (node (ref "U3") (pin "7") (pinfunction "DMINUS_7") (pintype "bidirectional"))
    )
    (net (code "73") (name "unconnected-(U3-DPLUS-Pad6)") (class "Default")
      (node (ref "U3") (pin "6") (pinfunction "DPLUS_6") (pintype "bidirectional"))
    )
    (net (code "74") (name "unconnected-(U6-NC-PadP$3)") (class "Default")
      (node (ref "U6") (pin "P$3") (pinfunction "NC_P$3") (pintype "passive"))
    )
    (net (code "75") (name "unconnected-(U12-PadCD2)") (class "Default")
      (node (ref "U12") (pin "CD2") (pinfunction "CD2_CD2") (pintype "bidirectional"))
    )
    (net (code "76") (name "unconnected-(U12-PadNC)") (class "Default")
      (node (ref "U12") (pin "NC") (pinfunction "NC_NC") (pintype "bidirectional"))
    )
  )
)
